# Sensor.net
KiCad netlist of a schematic drawn in EAGLE
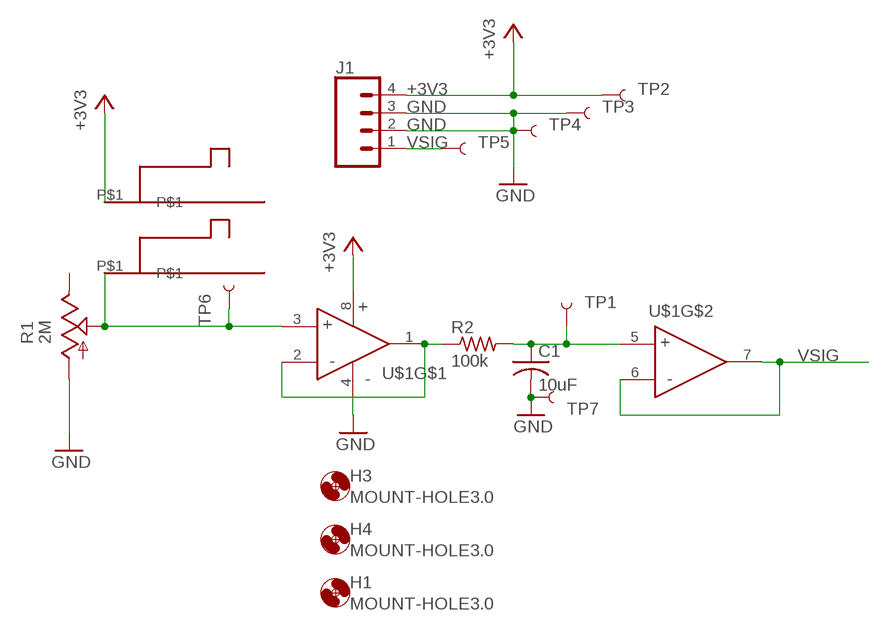
[diagram p0: schematic, sheet 1]

(export (version "E")
  (design (tool "Eeschema 10.0.6"))
  (components
    (comp (ref "C1")
      (value "10uF")
      (footprint "eagle-import:C1206")
      (libsource (lib "eagle-import") (part "C-USC1206"))
    )
    (comp (ref "H1")
      (value "MOUNT-HOLE3.0")
      (footprint "eagle-import:3,0")
      (libsource (lib "eagle-import") (part "MOUNT-HOLE3.0"))
    )
    (comp (ref "H3")
      (value "MOUNT-HOLE3.0")
      (footprint "eagle-import:3,0")
      (libsource (lib "eagle-import") (part "MOUNT-HOLE3.0"))
    )
    (comp (ref "H4")
      (value "MOUNT-HOLE3.0")
      (footprint "eagle-import:3,0")
      (libsource (lib "eagle-import") (part "MOUNT-HOLE3.0"))
    )
    (comp (ref "J1")
      (value "CONN_04SCREW")
      (footprint "eagle-import:SCREWTERMINAL-3.5MM-4")
      (libsource (lib "eagle-import") (part "CONN_04SCREW"))
    )
    (comp (ref "R1")
      (value "2M")
      (footprint "eagle-import:CT6")
      (libsource (lib "eagle-import") (part "TRIM_US-CT6"))
    )
    (comp (ref "R2")
      (value "100k")
      (footprint "eagle-import:R1206")
      (libsource (lib "eagle-import") (part "R-US_R1206"))
    )
    (comp (ref "TP1")
      (value "TEST-POINT3X5")
      (footprint "eagle-import:PAD.03X.05")
      (libsource (lib "eagle-import") (part "TEST-POINT3X5"))
    )
    (comp (ref "TP2")
      (value "TEST-POINT3X5")
      (footprint "eagle-import:PAD.03X.05")
      (libsource (lib "eagle-import") (part "TEST-POINT3X5"))
    )
    (comp (ref "TP3")
      (value "TEST-POINT3X5")
      (footprint "eagle-import:PAD.03X.05")
      (libsource (lib "eagle-import") (part "TEST-POINT3X5"))
    )
    (comp (ref "TP4")
      (value "TEST-POINT3X5")
      (footprint "eagle-import:PAD.03X.05")
      (libsource (lib "eagle-import") (part "TEST-POINT3X5"))
    )
    (comp (ref "TP5")
      (value "TEST-POINT3X5")
      (footprint "eagle-import:PAD.03X.05")
      (libsource (lib "eagle-import") (part "TEST-POINT3X5"))
    )
    (comp (ref "TP6")
      (value "TEST-POINT3X5")
      (footprint "eagle-import:PAD.03X.05")
      (libsource (lib "eagle-import") (part "TEST-POINT3X5"))
    )
    (comp (ref "TP7")
      (value "TEST-POINT3X5")
      (footprint "eagle-import:PAD.03X.05")
      (libsource (lib "eagle-import") (part "TEST-POINT3X5"))
    )
    (comp (ref "U$1")
      (value "TLV9102")
      (footprint "eagle-import:SOIC-8")
      (libsource (lib "eagle-import") (part "TLV9102"))
    )
    (comp (ref "U$2")
      (value "709155001610004")
      (footprint "eagle-import:709155001610004")
      (libsource (lib "eagle-import") (part "709155001610004"))
    )
    (comp (ref "U$3")
      (value "709155001610004")
      (footprint "eagle-import:709155001610004")
      (libsource (lib "eagle-import") (part "709155001610004"))
    )
  )
  (nets
    (net (code "1") (name "+3V3") (class "Default")
      (node (ref "J1") (pin "4") (pinfunction "4_4") (pintype "passive"))
      (node (ref "TP2") (pin "P$1") (pinfunction "1_P$1") (pintype "bidirectional"))
      (node (ref "U$1") (pin "8") (pinfunction "V+_8") (pintype "bidirectional"))
      (node (ref "U$2") (pin "P$1") (pinfunction "P$1_P$1") (pintype "bidirectional"))
    )
    (net (code "2") (name "/VSIG") (class "Default")
      (node (ref "J1") (pin "1") (pinfunction "1_1") (pintype "passive"))
      (node (ref "TP5") (pin "P$1") (pinfunction "1_P$1") (pintype "bidirectional"))
      (node (ref "U$1") (pin "6") (pinfunction "-_6") (pintype "input"))
      (node (ref "U$1") (pin "7") (pinfunction "OUT_7") (pintype "output"))
    )
    (net (code "3") (name "GND") (class "Default")
      (node (ref "C1") (pin "2") (pinfunction "2_2") (pintype "passive"))
      (node (ref "J1") (pin "2") (pinfunction "2_2") (pintype "passive"))
      (node (ref "J1") (pin "3") (pinfunction "3_3") (pintype "passive"))
      (node (ref "R1") (pin "A") (pinfunction "A_A") (pintype "passive"))
      (node (ref "TP3") (pin "P$1") (pinfunction "1_P$1") (pintype "bidirectional"))
      (node (ref "TP4") (pin "P$1") (pinfunction "1_P$1") (pintype "bidirectional"))
      (node (ref "TP7") (pin "P$1") (pinfunction "1_P$1") (pintype "bidirectional"))
      (node (ref "U$1") (pin "4") (pinfunction "V-_4") (pintype "bidirectional"))
    )
    (net (code "4") (name "Net-(TP1-1)") (class "Default")
      (node (ref "C1") (pin "1") (pinfunction "1_1") (pintype "passive"))
      (node (ref "R2") (pin "2") (pinfunction "2_2") (pintype "passive"))
      (node (ref "TP1") (pin "P$1") (pinfunction "1_P$1") (pintype "bidirectional"))
      (node (ref "U$1") (pin "5") (pinfunction "+_5") (pintype "input"))
    )
    (net (code "5") (name "Net-(TP6-1)") (class "Default")
      (node (ref "R1") (pin "S") (pinfunction "S_S") (pintype "passive"))
      (node (ref "TP6") (pin "P$1") (pinfunction "1_P$1") (pintype "bidirectional"))
      (node (ref "U$1") (pin "3") (pinfunction "NONINVERTING_3") (pintype "input"))
      (node (ref "U$3") (pin "P$1") (pinfunction "P$1_P$1") (pintype "bidirectional"))
    )
    (net (code "6") (name "Net-(U$1A-INVERTING)") (class "Default")
      (node (ref "R2") (pin "1") (pinfunction "1_1") (pintype "passive"))
      (node (ref "U$1") (pin "1") (pinfunction "OUT_1") (pintype "output"))
      (node (ref "U$1") (pin "2") (pinfunction "INVERTING_2") (pintype "input"))
    )
    (net (code "7") (name "unconnected-(R1-PadE)") (class "Default")
      (node (ref "R1") (pin "E") (pinfunction "E_E") (pintype "passive"))
    )
  )
)
